# mag_encoder_Rev3_single_sided_1.net
KiCad netlist of a schematic drawn in EAGLE
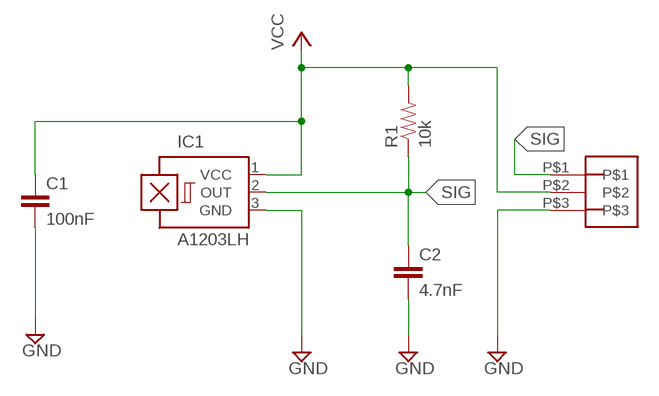
[diagram p0: schematic, sheet 1]

(export (version "E")
  (design (tool "Eeschema 10.0.6"))
  (components
    (comp (ref "C1")
      (value "100nF")
      (footprint "eagle-import:0603-CAP")
      (libsource (lib "eagle-import") (part "CAP0603-CAP"))
    )
    (comp (ref "C2")
      (value "4.7nF")
      (footprint "eagle-import:0603-CAP")
      (libsource (lib "eagle-import") (part "4.7NF-50V-10%(0603)"))
    )
    (comp (ref "IC1")
      (value "A1203LH")
      (footprint "eagle-import:SOT23-W")
      (fields (field (name "MF") "ALLEGRO MICROSYSTEMS, INC.") (field (name "MPN") "A1203LLHLT-T"))
      (libsource (lib "eagle-import") (part "A12?LH03"))
    )
    (comp (ref "R1")
      (value "10k")
      (footprint "eagle-import:0603")
      (libsource (lib "eagle-import") (part "10.5KOHM1/10W1%(0603)"))
    )
    (comp (ref "U$1")
      (value "3_PIN_JST-XH")
      (footprint "eagle-import:3_PIN_JST-XH")
      (libsource (lib "eagle-import") (part "3_PIN_JST-XH"))
    )
  )
  (nets
    (net (code "1") (name "GND") (class "Default")
      (node (ref "C1") (pin "2") (pinfunction "2_2") (pintype "passive"))
      (node (ref "C2") (pin "2") (pinfunction "2_2") (pintype "passive"))
      (node (ref "IC1") (pin "3") (pinfunction "GND_3") (pintype "power_in"))
      (node (ref "U$1") (pin "P$3") (pinfunction "P$3_P$3") (pintype "bidirectional"))
    )
    (net (code "2") (name "SIG") (class "Default")
      (node (ref "C2") (pin "1") (pinfunction "1_1") (pintype "passive"))
      (node (ref "IC1") (pin "2") (pinfunction "OUT_2") (pintype "output"))
      (node (ref "R1") (pin "1") (pinfunction "1_1") (pintype "passive"))
      (node (ref "U$1") (pin "P$1") (pinfunction "P$1_P$1") (pintype "bidirectional"))
    )
    (net (code "3") (name "VCC") (class "Default")
      (node (ref "C1") (pin "1") (pinfunction "1_1") (pintype "passive"))
      (node (ref "IC1") (pin "1") (pinfunction "VCC_1") (pintype "power_in"))
      (node (ref "R1") (pin "2") (pinfunction "2_2") (pintype "passive"))
      (node (ref "U$1") (pin "P$2") (pinfunction "P$2_P$2") (pintype "bidirectional"))
    )
  )
)
